# CL_LFR_V2.net
KiCad netlist of a schematic drawn in EasyEDA Pro
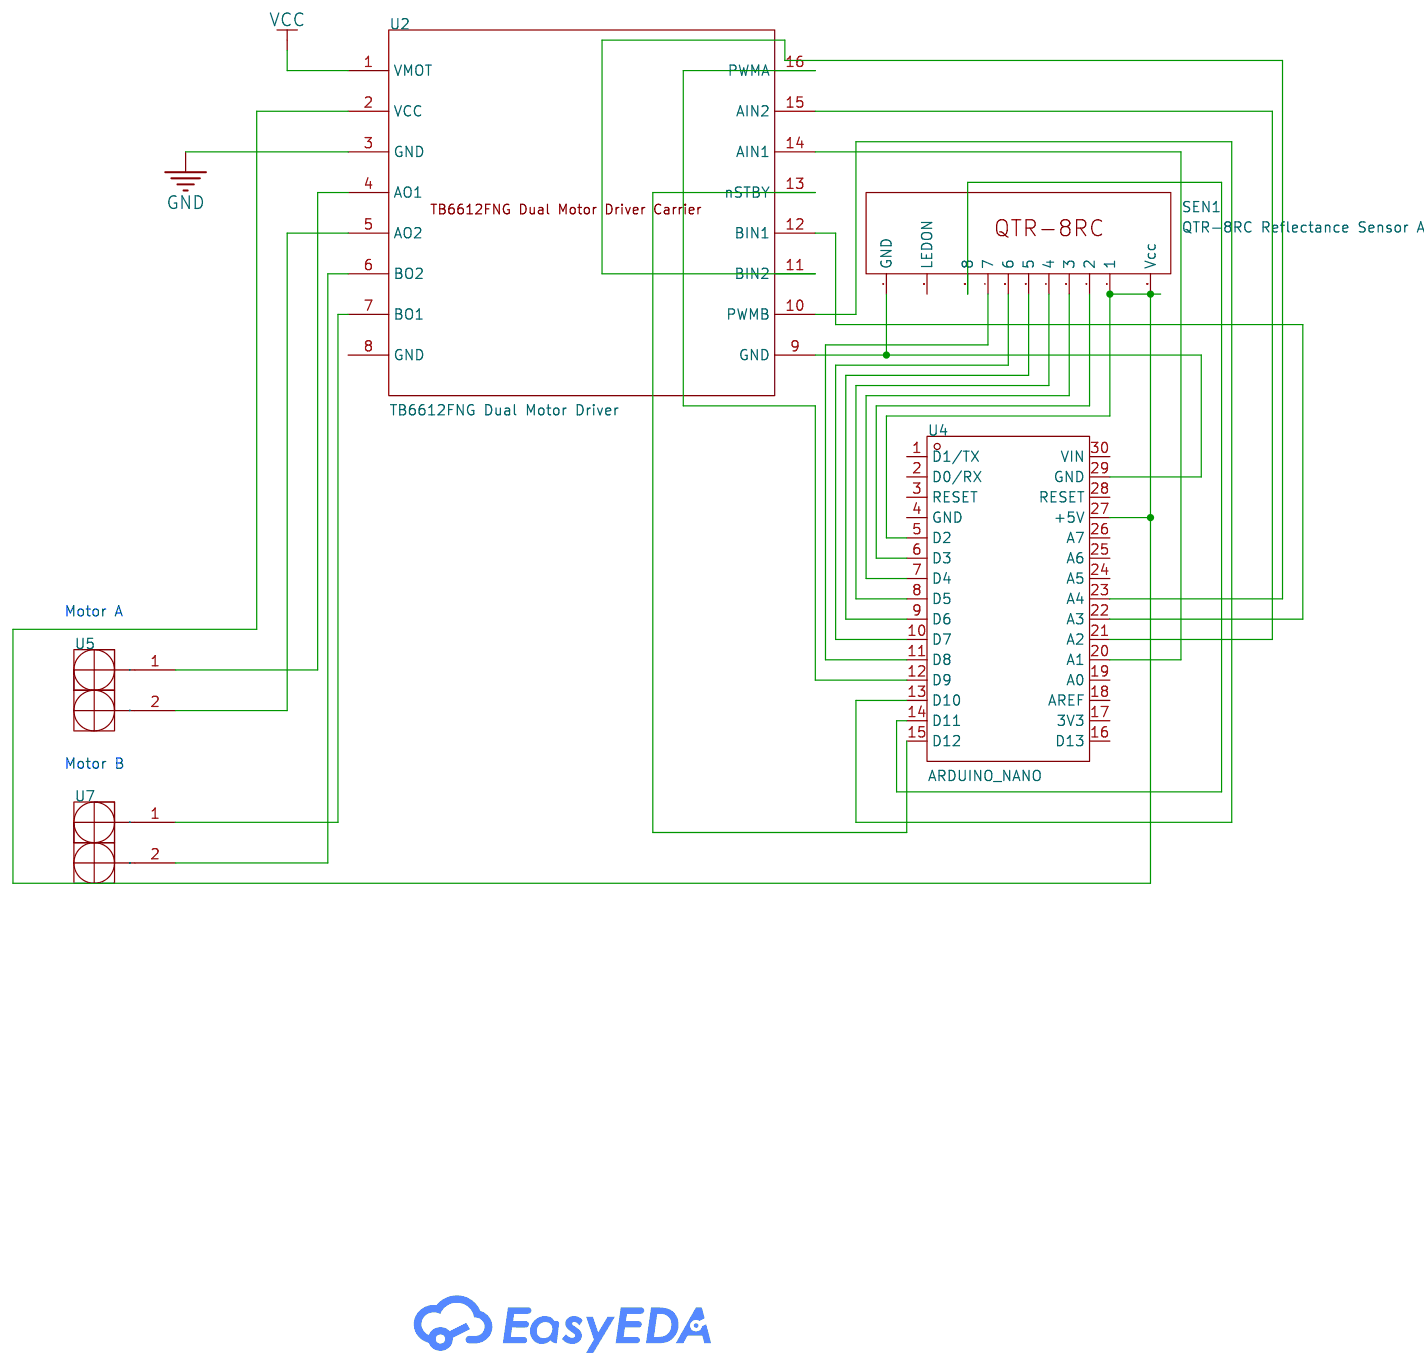
[diagram p0: schematic sheet]

(export (version "E")
  (design (tool "Eeschema 10.0.6"))
  (components
    (comp (ref "SEN1")
      (value "QTR-8RC Reflectance Sensor Array")
      (footprint "easyedapro:QTR-8X")
      (fields (field (name "Manufacturer") "Pololu"))
      (libsource (lib "easyedapro") (part "QTR-8RC Reflectance Sensor Array"))
    )
    (comp (ref "U2")
      (value "TB6612FNG Dual Motor Driver")
      (footprint "easyedapro:TB6612FNG")
      (libsource (lib "easyedapro") (part "TB6612FNG Dual Motor Driver"))
    )
    (comp (ref "U4")
      (value "ARDUINO_NANO")
      (footprint "easyedapro:COMM-TH_ARDUINO_NANO")
      (libsource (lib "easyedapro") (part "ARDUINO_NANO"))
    )
    (comp (ref "U5")
      (value "~")
      (footprint "easyedapro:2PIN SCREW TERMINAL")
      (libsource (lib "easyedapro") (part "2PIN SCREW TERMINAL"))
    )
    (comp (ref "U7")
      (value "~")
      (footprint "easyedapro:2PIN SCREW TERMINAL")
      (libsource (lib "easyedapro") (part "2PIN SCREW TERMINAL"))
    )
  )
  (nets
    (net (code "1") (name "GND") (class "Default")
      (node (ref "U2") (pin "3") (pinfunction "GND_3") (pintype "unspecified"))
    )
    (net (code "2") (name "Net-(SEN1-GND)") (class "Default")
      (node (ref "SEN1") (pin "11") (pinfunction "GND_11") (pintype "unspecified"))
      (node (ref "U2") (pin "9") (pinfunction "GND_9") (pintype "unspecified"))
      (node (ref "U4") (pin "29") (pinfunction "GND_29") (pintype "unspecified"))
    )
    (net (code "3") (name "Net-(SEN1-Vcc)") (class "Default")
      (node (ref "SEN1") (pin "1") (pinfunction "1_1") (pintype "unspecified"))
      (node (ref "SEN1") (pin "10") (pinfunction "Vcc_10") (pintype "unspecified"))
      (node (ref "U2") (pin "2") (pinfunction "VCC_2") (pintype "unspecified"))
      (node (ref "U4") (pin "27") (pinfunction "+5V_27") (pintype "unspecified"))
      (node (ref "U4") (pin "5") (pinfunction "D2_5") (pintype "unspecified"))
    )
    (net (code "4") (name "Net-(U2-AIN1)") (class "Default")
      (node (ref "U2") (pin "14") (pinfunction "AIN1_14") (pintype "unspecified"))
      (node (ref "U4") (pin "20") (pinfunction "A1_20") (pintype "unspecified"))
    )
    (net (code "5") (name "Net-(U2-AIN2)") (class "Default")
      (node (ref "U2") (pin "15") (pinfunction "AIN2_15") (pintype "unspecified"))
      (node (ref "U4") (pin "21") (pinfunction "A2_21") (pintype "unspecified"))
    )
    (net (code "6") (name "Net-(U2-AO1)") (class "Default")
      (node (ref "U2") (pin "4") (pinfunction "AO1_4") (pintype "unspecified"))
      (node (ref "U5") (pin "1") (pinfunction "1_1") (pintype "input"))
    )
    (net (code "7") (name "Net-(U2-AO2)") (class "Default")
      (node (ref "U2") (pin "5") (pinfunction "AO2_5") (pintype "unspecified"))
      (node (ref "U5") (pin "2") (pinfunction "2_2") (pintype "input"))
    )
    (net (code "8") (name "Net-(U2-BIN1)") (class "Default")
      (node (ref "U2") (pin "12") (pinfunction "BIN1_12") (pintype "unspecified"))
      (node (ref "U4") (pin "22") (pinfunction "A3_22") (pintype "unspecified"))
    )
    (net (code "9") (name "Net-(U2-BIN2)") (class "Default")
      (node (ref "U2") (pin "11") (pinfunction "BIN2_11") (pintype "unspecified"))
      (node (ref "U4") (pin "23") (pinfunction "A4_23") (pintype "unspecified"))
    )
    (net (code "10") (name "Net-(U2-BO1)") (class "Default")
      (node (ref "U2") (pin "7") (pinfunction "BO1_7") (pintype "unspecified"))
      (node (ref "U7") (pin "1") (pinfunction "1_1") (pintype "input"))
    )
    (net (code "11") (name "Net-(U2-BO2)") (class "Default")
      (node (ref "U2") (pin "6") (pinfunction "BO2_6") (pintype "unspecified"))
      (node (ref "U7") (pin "2") (pinfunction "2_2") (pintype "input"))
    )
    (net (code "12") (name "Net-(U2-PWMA)") (class "Default")
      (node (ref "U2") (pin "16") (pinfunction "PWMA_16") (pintype "unspecified"))
      (node (ref "U4") (pin "12") (pinfunction "D9_12") (pintype "unspecified"))
    )
    (net (code "13") (name "Net-(U2-PWMB)") (class "Default")
      (node (ref "U2") (pin "10") (pinfunction "PWMB_10") (pintype "unspecified"))
      (node (ref "U4") (pin "13") (pinfunction "D10_13") (pintype "unspecified"))
    )
    (net (code "14") (name "Net-(U2-nSTBY)") (class "Default")
      (node (ref "U2") (pin "13") (pinfunction "nSTBY_13") (pintype "unspecified"))
      (node (ref "U4") (pin "15") (pinfunction "D12_15") (pintype "unspecified"))
    )
    (net (code "15") (name "Net-(U4-D3)") (class "Default")
      (node (ref "SEN1") (pin "2") (pinfunction "2_2") (pintype "unspecified"))
      (node (ref "U4") (pin "6") (pinfunction "D3_6") (pintype "unspecified"))
    )
    (net (code "16") (name "Net-(U4-D4)") (class "Default")
      (node (ref "SEN1") (pin "3") (pinfunction "3_3") (pintype "unspecified"))
      (node (ref "U4") (pin "7") (pinfunction "D4_7") (pintype "unspecified"))
    )
    (net (code "17") (name "Net-(U4-D5)") (class "Default")
      (node (ref "SEN1") (pin "4") (pinfunction "4_4") (pintype "unspecified"))
      (node (ref "U4") (pin "8") (pinfunction "D5_8") (pintype "unspecified"))
    )
    (net (code "18") (name "Net-(U4-D6)") (class "Default")
      (node (ref "SEN1") (pin "5") (pinfunction "5_5") (pintype "unspecified"))
      (node (ref "U4") (pin "9") (pinfunction "D6_9") (pintype "unspecified"))
    )
    (net (code "19") (name "Net-(U4-D7)") (class "Default")
      (node (ref "SEN1") (pin "6") (pinfunction "6_6") (pintype "unspecified"))
      (node (ref "U4") (pin "10") (pinfunction "D7_10") (pintype "unspecified"))
    )
    (net (code "20") (name "Net-(U4-D8)") (class "Default")
      (node (ref "SEN1") (pin "7") (pinfunction "7_7") (pintype "unspecified"))
      (node (ref "U4") (pin "11") (pinfunction "D8_11") (pintype "unspecified"))
    )
    (net (code "21") (name "Net-(U4-D11)") (class "Default")
      (node (ref "SEN1") (pin "8") (pinfunction "8_8") (pintype "unspecified"))
      (node (ref "U4") (pin "14") (pinfunction "D11_14") (pintype "unspecified"))
    )
    (net (code "22") (name "VCC") (class "Default")
      (node (ref "U2") (pin "1") (pinfunction "VMOT_1") (pintype "unspecified"))
    )
    (net (code "23") (name "unconnected-(SEN1-LEDON-Pad9)") (class "Default")
      (node (ref "SEN1") (pin "9") (pinfunction "LEDON_9") (pintype "unspecified"))
    )
    (net (code "24") (name "unconnected-(U2-GND-Pad8)") (class "Default")
      (node (ref "U2") (pin "8") (pinfunction "GND_8") (pintype "unspecified"))
    )
    (net (code "25") (name "unconnected-(U4-3V3-Pad17)") (class "Default")
      (node (ref "U4") (pin "17") (pinfunction "3V3_17") (pintype "unspecified"))
    )
    (net (code "26") (name "unconnected-(U4-A0-Pad19)") (class "Default")
      (node (ref "U4") (pin "19") (pinfunction "A0_19") (pintype "unspecified"))
    )
    (net (code "27") (name "unconnected-(U4-A5-Pad24)") (class "Default")
      (node (ref "U4") (pin "24") (pinfunction "A5_24") (pintype "unspecified"))
    )
    (net (code "28") (name "unconnected-(U4-A6-Pad25)") (class "Default")
      (node (ref "U4") (pin "25") (pinfunction "A6_25") (pintype "unspecified"))
    )
    (net (code "29") (name "unconnected-(U4-A7-Pad26)") (class "Default")
      (node (ref "U4") (pin "26") (pinfunction "A7_26") (pintype "unspecified"))
    )
    (net (code "30") (name "unconnected-(U4-AREF-Pad18)") (class "Default")
      (node (ref "U4") (pin "18") (pinfunction "AREF_18") (pintype "unspecified"))
    )
    (net (code "31") (name "unconnected-(U4-D0{slash}RX-Pad2)") (class "Default")
      (node (ref "U4") (pin "2") (pinfunction "D0/RX_2") (pintype "unspecified"))
    )
    (net (code "32") (name "unconnected-(U4-D1{slash}TX-Pad1)") (class "Default")
      (node (ref "U4") (pin "1") (pinfunction "D1/TX_1") (pintype "unspecified"))
    )
    (net (code "33") (name "unconnected-(U4-D13-Pad16)") (class "Default")
      (node (ref "U4") (pin "16") (pinfunction "D13_16") (pintype "unspecified"))
    )
    (net (code "34") (name "unconnected-(U4-GND-Pad4)") (class "Default")
      (node (ref "U4") (pin "4") (pinfunction "GND_4") (pintype "unspecified"))
    )
    (net (code "35") (name "unconnected-(U4-RESET-Pad3)") (class "Default")
      (node (ref "U4") (pin "3") (pinfunction "RESET_3") (pintype "unspecified"))
    )
    (net (code "36") (name "unconnected-(U4-RESET-Pad28)") (class "Default")
      (node (ref "U4") (pin "28") (pinfunction "RESET_28") (pintype "unspecified"))
    )
    (net (code "37") (name "unconnected-(U4-VIN-Pad30)") (class "Default")
      (node (ref "U4") (pin "30") (pinfunction "VIN_30") (pintype "unspecified"))
    )
  )
)
